# Full_Bridge_Inverter.net
KiCad netlist of a schematic drawn in Altium Designer
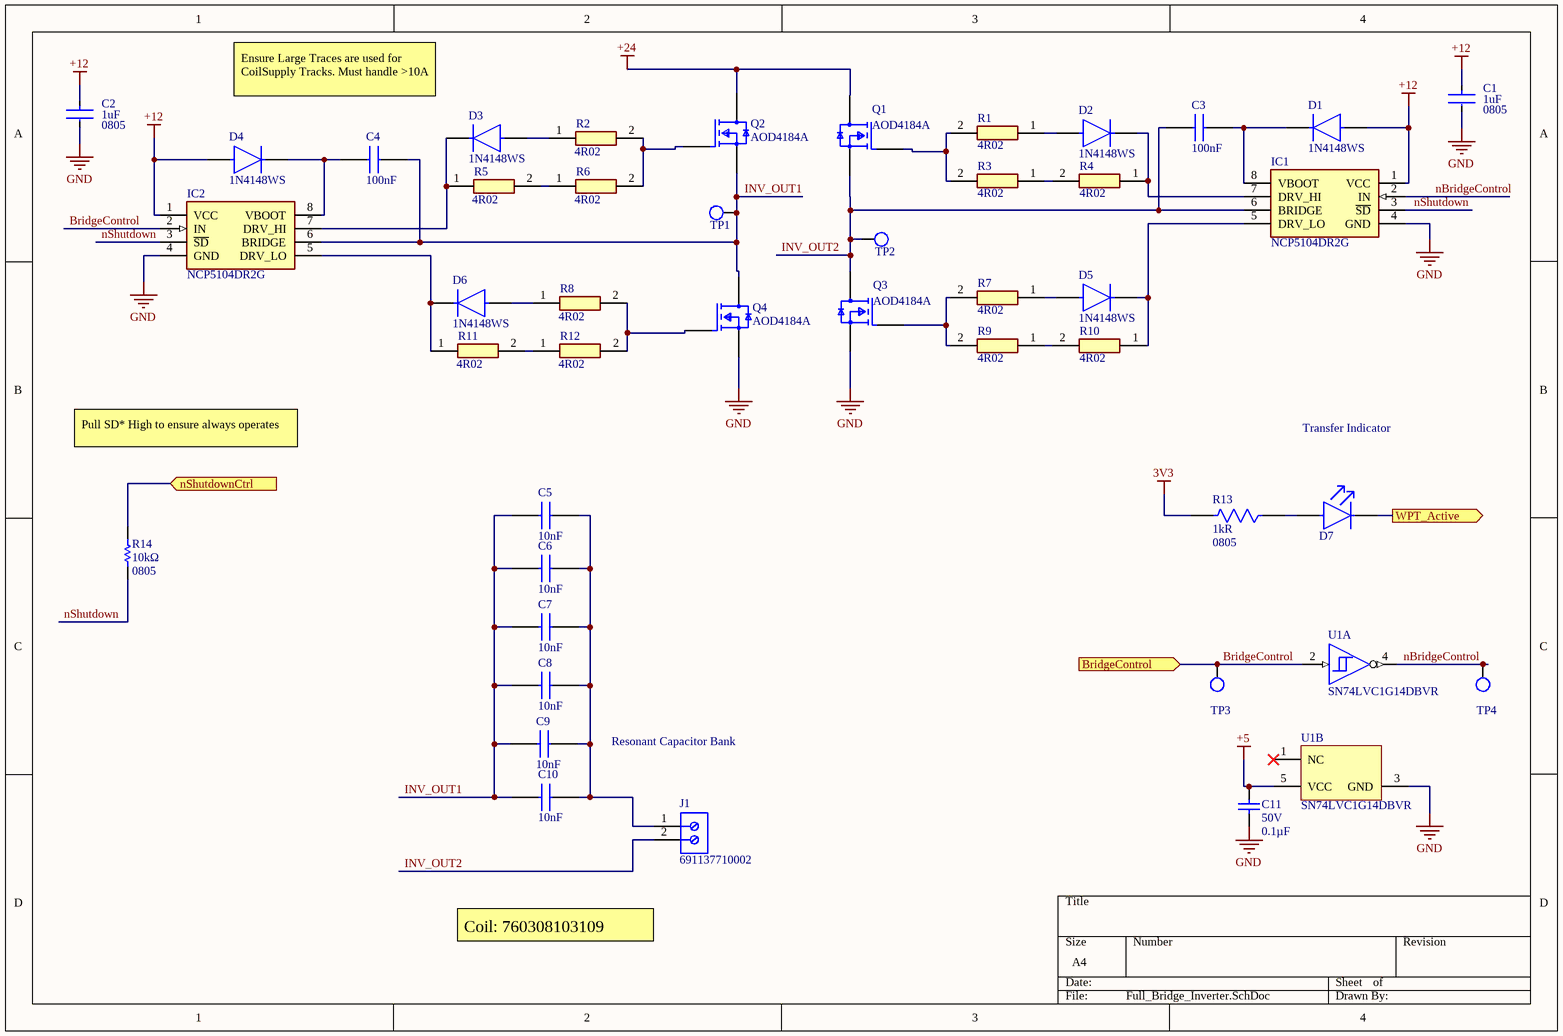
[diagram p0: Full_Bridge_Inverter.SchDoc]

(export (version "E")
  (design (tool "Eeschema 10.0.6"))
  (components
    (comp (ref "C1")
      (value "885012207078")
      (footprint "FP-885012207078-MFG")
      (description "CAP CER 1UF 25V X7R 0805")
      (fields
        (field (name "CAPACITANCE") "1uF")
        (field (name "CASE CODE (IMPERIAL)") "0805")
        (field (name "TOLERANCE") "10%")
      )
      (libsource (lib "Altium Content Vault") (part "b4654b650e69147ec39a6b967a45e02"))
    )
    (comp (ref "C2")
      (value "885012207078")
      (footprint "FP-885012207078-MFG")
      (description "CAP CER 1UF 25V X7R 0805")
      (fields
        (field (name "CAPACITANCE") "1uF")
        (field (name "CASE CODE (IMPERIAL)") "0805")
        (field (name "TOLERANCE") "10%")
      )
      (libsource (lib "Altium Content Vault") (part "b4654b650e69147ec39a6b967a45e02"))
    )
    (comp (ref "C3")
      (value "C0805C104K1RACAUTO7210")
      (footprint "C0805")
      (description "Capacitor")
      (fields (field (name "MOUSER PART NUMBER") "80-C0805C104K1RAUTLR") (field (name "CAPACITANCE") "100nF"))
      (libsource (lib "WPT_Transmitter_lib") (part "C0805C104K1RACAUTO7210"))
    )
    (comp (ref "C4")
      (value "C0805C104K1RACAUTO7210")
      (footprint "C0805")
      (description "Capacitor")
      (fields (field (name "MOUSER PART NUMBER") "80-C0805C104K1RAUTLR") (field (name "CAPACITANCE") "100nF"))
      (libsource (lib "WPT_Transmitter_lib") (part "C0805C104K1RACAUTO7210"))
    )
    (comp (ref "C5")
      (value "C1206C103JAGECAUTO")
      (footprint "SamacSys:CAPC3216X110N")
      (description "Capacitor")
      (fields (field (name "MOUSER PART NUMBER") "80-C1206C103JAGECAUT") (field (name "CAPACITANCE") "10nF"))
      (libsource (lib "*") (part "C1206C103JAGECAUTO"))
    )
    (comp (ref "C6")
      (value "C1206C103JAGECAUTO")
      (footprint "SamacSys:CAPC3216X110N")
      (description "Capacitor")
      (fields (field (name "MOUSER PART NUMBER") "80-C1206C103JAGECAUT") (field (name "CAPACITANCE") "10nF"))
      (libsource (lib "*") (part "C1206C103JAGECAUTO"))
    )
    (comp (ref "C7")
      (value "C1206C103JAGECAUTO")
      (footprint "SamacSys:CAPC3216X110N")
      (description "Capacitor")
      (fields (field (name "MOUSER PART NUMBER") "80-C1206C103JAGECAUT") (field (name "CAPACITANCE") "10nF"))
      (libsource (lib "*") (part "C1206C103JAGECAUTO"))
    )
    (comp (ref "C8")
      (value "C1206C103JAGECAUTO")
      (footprint "SamacSys:CAPC3216X110N")
      (description "Capacitor")
      (fields (field (name "MOUSER PART NUMBER") "80-C1206C103JAGECAUT") (field (name "CAPACITANCE") "10nF"))
      (libsource (lib "*") (part "C1206C103JAGECAUTO"))
    )
    (comp (ref "C9")
      (value "C1206C103JAGECAUTO")
      (footprint "SamacSys:CAPC3216X110N")
      (description "Capacitor")
      (fields (field (name "MOUSER PART NUMBER") "80-C1206C103JAGECAUT") (field (name "CAPACITANCE") "10nF"))
      (libsource (lib "*") (part "C1206C103JAGECAUTO"))
    )
    (comp (ref "C10")
      (value "C1206C103JAGECAUTO")
      (footprint "SamacSys:CAPC3216X110N")
      (description "Capacitor")
      (fields (field (name "MOUSER PART NUMBER") "80-C1206C103JAGECAUT") (field (name "CAPACITANCE") "10nF"))
      (libsource (lib "*") (part "C1206C103JAGECAUTO"))
    )
    (comp (ref "C11")
      (value "C0805C104K5RACTU")
      (footprint "CAP0805")
      (description "CAP CER 0.1UF 50V X7R 0805")
      (fields
        (field (name "TOLERANCE") "±10%")
        (field (name "VOLTAGE - RATED") "50V")
        (field (name "CAPACITANCE") "0.1µF")
      )
      (libsource (lib "Capacitors") (part "C0805C104K5RACTU"))
    )
    (comp (ref "D1")
      (value "1N4148WS")
      (footprint "FP-477AB-IPC_C")
      (description "DIODE GEN PURP 75V 150MA SOD323F")
      (libsource (lib "Altium Content Vault") (part "d7152d700b627762746794eb795d46e"))
    )
    (comp (ref "D2")
      (value "1N4148WS")
      (footprint "FP-477AB-IPC_C")
      (description "DIODE GEN PURP 75V 150MA SOD323F")
      (libsource (lib "Altium Content Vault") (part "d7152d700b627762746794eb795d46e"))
    )
    (comp (ref "D3")
      (value "1N4148WS")
      (footprint "FP-477AB-IPC_C")
      (description "DIODE GEN PURP 75V 150MA SOD323F")
      (libsource (lib "Altium Content Vault") (part "d7152d700b627762746794eb795d46e"))
    )
    (comp (ref "D4")
      (value "1N4148WS")
      (footprint "FP-477AB-IPC_C")
      (description "DIODE GEN PURP 75V 150MA SOD323F")
      (libsource (lib "Altium Content Vault") (part "d7152d700b627762746794eb795d46e"))
    )
    (comp (ref "D5")
      (value "1N4148WS")
      (footprint "FP-477AB-IPC_C")
      (description "DIODE GEN PURP 75V 150MA SOD323F")
      (libsource (lib "Altium Content Vault") (part "d7152d700b627762746794eb795d46e"))
    )
    (comp (ref "D6")
      (value "1N4148WS")
      (footprint "FP-477AB-IPC_C")
      (description "DIODE GEN PURP 75V 150MA SOD323F")
      (libsource (lib "Altium Content Vault") (part "d7152d700b627762746794eb795d46e"))
    )
    (comp (ref "D7")
      (value "150060VS75000")
      (footprint "FP-150060VS75000-MFG")
      (description "LED GREEN CLEAR 0603 SMD")
      (libsource (lib "Altium Content Vault") (part "8706943c75ba83719d021d2fdc84c58"))
    )
    (comp (ref "IC1")
      (value "NCP5104DR2G")
      (footprint "WPT_Transmitter_lib:SOIC127P600X175-8N")
      (description "Integrated Circuit")
      (fields (field (name "MOUSER PART NUMBER") "863-NCP5104DR2G"))
      (libsource (lib "") (part "NCP5104DR2G_1"))
    )
    (comp (ref "IC2")
      (value "NCP5104DR2G")
      (footprint "WPT_Transmitter_lib:SOIC127P600X175-8N")
      (description "Integrated Circuit")
      (fields (field (name "MOUSER PART NUMBER") "863-NCP5104DR2G"))
      (libsource (lib "WPT_Transmitter_lib") (part "NCP5104DR2G"))
    )
    (comp (ref "J1")
      (value "691137710002")
      (footprint "691137710002")
      (description "Series 1377 - 5.00 mm Horizontal Entry with Pressure Clamp WR-TBL, 2 pin")
      (fields (field (name "MANUFACTURER") "Wurth Elektronik") (field (name "PUBLISHER") "WurthElektronik"))
      (libsource (lib "Altium Content Vault") (part "WE-CN-1P-F-TB2"))
    )
    (comp (ref "Q1")
      (value "AOD4184A")
      (footprint "FP-TO252-MFG")
      (description "MOSFET N-CH 40V 50A TO252")
      (libsource (lib "Altium Content Vault") (part "eaf820099600a16e7148a0c70285cb7"))
    )
    (comp (ref "Q2")
      (value "AOD4184A")
      (footprint "FP-TO252-MFG")
      (description "MOSFET N-CH 40V 50A TO252")
      (libsource (lib "Altium Content Vault") (part "eaf820099600a16e7148a0c70285cb7"))
    )
    (comp (ref "Q3")
      (value "AOD4184A")
      (footprint "FP-TO252-MFG")
      (description "MOSFET N-CH 40V 50A TO252")
      (libsource (lib "Altium Content Vault") (part "eaf820099600a16e7148a0c70285cb7"))
    )
    (comp (ref "Q4")
      (value "AOD4184A")
      (footprint "FP-TO252-MFG")
      (description "MOSFET N-CH 40V 50A TO252")
      (libsource (lib "Altium Content Vault") (part "eaf820099600a16e7148a0c70285cb7"))
    )
    (comp (ref "R1")
      (value "RMCF1206FT4R02")
      (footprint "WPT_Transmitter_lib:RESC3216X70N")
      (description "Resistor")
      (fields (field (name "RESISTANCE") "4R02"))
      (libsource (lib "") (part "RMCF1206FT4R02_1"))
    )
    (comp (ref "R2")
      (value "RMCF1206FT4R02")
      (footprint "WPT_Transmitter_lib:RESC3216X70N")
      (description "Resistor")
      (fields (field (name "RESISTANCE") "4R02"))
      (libsource (lib "WPT_Transmitter_lib") (part "RMCF1206FT4R02"))
    )
    (comp (ref "R3")
      (value "RMCF1206FT4R02")
      (footprint "WPT_Transmitter_lib:RESC3216X70N")
      (description "Resistor")
      (fields (field (name "RESISTANCE") "4R02"))
      (libsource (lib "") (part "RMCF1206FT4R02_1"))
    )
    (comp (ref "R4")
      (value "RMCF1206FT4R02")
      (footprint "WPT_Transmitter_lib:RESC3216X70N")
      (description "Resistor")
      (fields (field (name "RESISTANCE") "4R02"))
      (libsource (lib "") (part "RMCF1206FT4R02_1"))
    )
    (comp (ref "R5")
      (value "RMCF1206FT4R02")
      (footprint "WPT_Transmitter_lib:RESC3216X70N")
      (description "Resistor")
      (fields (field (name "RESISTANCE") "4R02"))
      (libsource (lib "WPT_Transmitter_lib") (part "RMCF1206FT4R02"))
    )
    (comp (ref "R6")
      (value "RMCF1206FT4R02")
      (footprint "WPT_Transmitter_lib:RESC3216X70N")
      (description "Resistor")
      (fields (field (name "RESISTANCE") "4R02"))
      (libsource (lib "WPT_Transmitter_lib") (part "RMCF1206FT4R02"))
    )
    (comp (ref "R7")
      (value "RMCF1206FT4R02")
      (footprint "WPT_Transmitter_lib:RESC3216X70N")
      (description "Resistor")
      (fields (field (name "RESISTANCE") "4R02"))
      (libsource (lib "") (part "RMCF1206FT4R02_1"))
    )
    (comp (ref "R8")
      (value "RMCF1206FT4R02")
      (footprint "WPT_Transmitter_lib:RESC3216X70N")
      (description "Resistor")
      (fields (field (name "RESISTANCE") "4R02"))
      (libsource (lib "WPT_Transmitter_lib") (part "RMCF1206FT4R02"))
    )
    (comp (ref "R9")
      (value "RMCF1206FT4R02")
      (footprint "WPT_Transmitter_lib:RESC3216X70N")
      (description "Resistor")
      (fields (field (name "RESISTANCE") "4R02"))
      (libsource (lib "") (part "RMCF1206FT4R02_1"))
    )
    (comp (ref "R10")
      (value "RMCF1206FT4R02")
      (footprint "WPT_Transmitter_lib:RESC3216X70N")
      (description "Resistor")
      (fields (field (name "RESISTANCE") "4R02"))
      (libsource (lib "") (part "RMCF1206FT4R02_1"))
    )
    (comp (ref "R11")
      (value "RMCF1206FT4R02")
      (footprint "WPT_Transmitter_lib:RESC3216X70N")
      (description "Resistor")
      (fields (field (name "RESISTANCE") "4R02"))
      (libsource (lib "WPT_Transmitter_lib") (part "RMCF1206FT4R02"))
    )
    (comp (ref "R12")
      (value "RMCF1206FT4R02")
      (footprint "WPT_Transmitter_lib:RESC3216X70N")
      (description "Resistor")
      (fields (field (name "RESISTANCE") "4R02"))
      (libsource (lib "WPT_Transmitter_lib") (part "RMCF1206FT4R02"))
    )
    (comp (ref "R13")
      (value "RNCP0805FTD1K00")
      (footprint "FP-RNCP0805-MFG")
      (description "1kΩ ±1% 0.25W 0805 High Power Anti-Sulfur Thin Film Chip Resistor")
      (fields
        (field (name "RESISTANCE") "1kR")
        (field (name "SIZE CODE") "0805")
        (field (name "TOLERANCE") "1%")
      )
      (libsource (lib "Altium Content Vault") (part "1029c3af85768c4190bb7ad29bc67b5"))
    )
    (comp (ref "R14")
      (value "RC0805FR-0710KL")
      (footprint "RES0805")
      (description "RES SMD 10K OHM 1% 1/8W 0805")
      (fields
        (field (name "MANUFACTURER") "Yageo")
        (field (name "TOLERANCE") "±1%")
        (field (name "RESISTANCE") "10kΩ")
        (field (name "PACKAGE / CASE") "0805")
      )
      (libsource (lib "Resistors") (part "RC0805FR-0710KL"))
    )
    (comp (ref "TP1")
      (value "Bridge 1")
      (footprint "TESTPOINT_LOOP")
      (description "PC TEST POINT MINIATURE WHITE")
      (libsource (lib "Connectors and Headers") (part "TESTPOINT_LOOP"))
    )
    (comp (ref "TP2")
      (value "Bridge 2")
      (footprint "TESTPOINT_LOOP")
      (description "PC TEST POINT MINIATURE WHITE")
      (libsource (lib "Connectors and Headers") (part "TESTPOINT_LOOP"))
    )
    (comp (ref "TP3")
      (value "Oscillator Out")
      (footprint "TESTPOINT_LOOP")
      (description "PC TEST POINT MINIATURE WHITE")
      (libsource (lib "Connectors and Headers") (part "TESTPOINT_LOOP"))
    )
    (comp (ref "TP4")
      (value "NOT Oscillator Out")
      (footprint "TESTPOINT_LOOP")
      (description "PC TEST POINT MINIATURE WHITE")
      (libsource (lib "Connectors and Headers") (part "TESTPOINT_LOOP"))
    )
    (comp (ref "U1")
      (value "SN74LVC1G14DBVR")
      (footprint "DBV0005A_L")
      (description "Single Schmitt-Trigger Inverter, DBV0005A, LARGE T&R")
      (fields
        (field (name "GENERIC PART NUMBER") "SN74LVC1G14")
        (field (name "MANUFACTURER") "Texas Instruments")
      )
      (libsource (lib "Altium Content Vault") (part "TI-SN74XXX1XX4-XX-5-SCHMITT"))
    )
  )
  (nets
    (net (code "1") (name "+5") (class "Default")
      (node (ref "C11") (pin "2") (pinfunction "2_2") (pintype "passive"))
      (node (ref "U1") (pin "5") (pinfunction "VCC_5") (pintype "power_in"))
    )
    (net (code "2") (name "+12") (class "Default")
      (node (ref "C1") (pin "1") (pinfunction "1_1") (pintype "passive"))
      (node (ref "C2") (pin "1") (pinfunction "1_1") (pintype "passive"))
      (node (ref "D1") (pin "2") (pinfunction "A_2") (pintype "passive"))
      (node (ref "D4") (pin "2") (pinfunction "A_2") (pintype "passive"))
      (node (ref "IC1") (pin "1") (pinfunction "VCC_1") (pintype "power_in"))
      (node (ref "IC2") (pin "1") (pinfunction "VCC_1") (pintype "power_in"))
    )
    (net (code "3") (name "+24") (class "Default")
      (node (ref "Q1") (pin "4") (pinfunction "D_4") (pintype "passive"))
      (node (ref "Q2") (pin "4") (pinfunction "D_4") (pintype "passive"))
    )
    (net (code "4") (name "/BridgeControl") (class "Default")
      (node (ref "IC2") (pin "2") (pinfunction "IN_2") (pintype "input"))
      (node (ref "TP3") (pin "1") (pintype "passive"))
      (node (ref "U1") (pin "2") (pinfunction "A_2") (pintype "input"))
    )
    (net (code "5") (name "/INV_OUT1") (class "Default")
      (node (ref "C10") (pin "2") (pinfunction "2_2") (pintype "passive"))
      (node (ref "C4") (pin "2") (pinfunction "2_2") (pintype "passive"))
      (node (ref "C5") (pin "1") (pinfunction "1_1") (pintype "passive"))
      (node (ref "C6") (pin "1") (pinfunction "1_1") (pintype "passive"))
      (node (ref "C7") (pin "1") (pinfunction "1_1") (pintype "passive"))
      (node (ref "C8") (pin "2") (pinfunction "2_2") (pintype "passive"))
      (node (ref "C9") (pin "2") (pinfunction "2_2") (pintype "passive"))
      (node (ref "IC2") (pin "6") (pinfunction "BRIDGE_6") (pintype "passive"))
      (node (ref "Q2") (pin "3") (pinfunction "S_3") (pintype "passive"))
      (node (ref "Q4") (pin "4") (pinfunction "D_4") (pintype "passive"))
      (node (ref "TP1") (pin "1") (pintype "passive"))
    )
    (net (code "6") (name "/INV_OUT2") (class "Default")
      (node (ref "C3") (pin "1") (pinfunction "1_1") (pintype "passive"))
      (node (ref "IC1") (pin "6") (pinfunction "BRIDGE_6") (pintype "passive"))
      (node (ref "J1") (pin "2") (pinfunction "2_2") (pintype "passive"))
      (node (ref "Q1") (pin "3") (pinfunction "S_3") (pintype "passive"))
      (node (ref "Q3") (pin "4") (pinfunction "D_4") (pintype "passive"))
      (node (ref "TP2") (pin "1") (pintype "passive"))
    )
    (net (code "7") (name "/WPT_Active") (class "Default")
      (node (ref "D7") (pin "1") (pinfunction "C_1") (pintype "passive"))
    )
    (net (code "8") (name "/nBridgeControl") (class "Default")
      (node (ref "IC1") (pin "2") (pinfunction "IN_2") (pintype "input"))
      (node (ref "TP4") (pin "1") (pintype "passive"))
      (node (ref "U1") (pin "4") (pinfunction "Y_4") (pintype "output"))
    )
    (net (code "9") (name "/nShutdown") (class "Default")
      (node (ref "IC1") (pin "3") (pinfunction "~{SD}_3") (pintype "passive"))
      (node (ref "IC2") (pin "3") (pinfunction "~{SD}_3") (pintype "passive"))
      (node (ref "R14") (pin "1") (pinfunction "1_1") (pintype "passive"))
    )
    (net (code "10") (name "/nShutdownCtrl") (class "Default")
      (node (ref "R14") (pin "2") (pinfunction "2_2") (pintype "passive"))
    )
    (net (code "11") (name "3V3") (class "Default")
      (node (ref "R13") (pin "2") (pinfunction "2_2") (pintype "passive"))
    )
    (net (code "12") (name "GND") (class "Default")
      (node (ref "C1") (pin "2") (pinfunction "2_2") (pintype "passive"))
      (node (ref "C11") (pin "1") (pinfunction "1_1") (pintype "passive"))
      (node (ref "C2") (pin "2") (pinfunction "2_2") (pintype "passive"))
      (node (ref "IC1") (pin "4") (pinfunction "GND_4") (pintype "power_in"))
      (node (ref "IC2") (pin "4") (pinfunction "GND_4") (pintype "power_in"))
      (node (ref "Q3") (pin "3") (pinfunction "S_3") (pintype "passive"))
      (node (ref "Q4") (pin "3") (pinfunction "S_3") (pintype "passive"))
      (node (ref "U1") (pin "3") (pinfunction "GND_3") (pintype "power_in"))
    )
    (net (code "13") (name "Net-(C10-Pad1)") (class "Default")
      (node (ref "C10") (pin "1") (pinfunction "1_1") (pintype "passive"))
      (node (ref "C5") (pin "2") (pinfunction "2_2") (pintype "passive"))
      (node (ref "C6") (pin "2") (pinfunction "2_2") (pintype "passive"))
      (node (ref "C7") (pin "2") (pinfunction "2_2") (pintype "passive"))
      (node (ref "C8") (pin "1") (pinfunction "1_1") (pintype "passive"))
      (node (ref "C9") (pin "1") (pinfunction "1_1") (pintype "passive"))
      (node (ref "J1") (pin "1") (pinfunction "1_1") (pintype "passive"))
    )
    (net (code "14") (name "Net-(D1-C)") (class "Default")
      (node (ref "C3") (pin "2") (pinfunction "2_2") (pintype "passive"))
      (node (ref "D1") (pin "1") (pinfunction "C_1") (pintype "passive"))
      (node (ref "IC1") (pin "8") (pinfunction "VBOOT_8") (pintype "passive"))
    )
    (net (code "15") (name "Net-(D2-A)") (class "Default")
      (node (ref "D2") (pin "2") (pinfunction "A_2") (pintype "passive"))
      (node (ref "R1") (pin "1") (pinfunction "1_1") (pintype "passive"))
    )
    (net (code "16") (name "Net-(D2-C)") (class "Default")
      (node (ref "D2") (pin "1") (pinfunction "C_1") (pintype "passive"))
      (node (ref "IC1") (pin "7") (pinfunction "DRV_HI_7") (pintype "passive"))
      (node (ref "R4") (pin "1") (pinfunction "1_1") (pintype "passive"))
    )
    (net (code "17") (name "Net-(D3-A)") (class "Default")
      (node (ref "D3") (pin "2") (pinfunction "A_2") (pintype "passive"))
      (node (ref "R2") (pin "1") (pinfunction "1_1") (pintype "passive"))
    )
    (net (code "18") (name "Net-(D3-C)") (class "Default")
      (node (ref "D3") (pin "1") (pinfunction "C_1") (pintype "passive"))
      (node (ref "IC2") (pin "7") (pinfunction "DRV_HI_7") (pintype "passive"))
      (node (ref "R5") (pin "1") (pinfunction "1_1") (pintype "passive"))
    )
    (net (code "19") (name "Net-(D4-C)") (class "Default")
      (node (ref "C4") (pin "1") (pinfunction "1_1") (pintype "passive"))
      (node (ref "D4") (pin "1") (pinfunction "C_1") (pintype "passive"))
      (node (ref "IC2") (pin "8") (pinfunction "VBOOT_8") (pintype "passive"))
    )
    (net (code "20") (name "Net-(D5-A)") (class "Default")
      (node (ref "D5") (pin "2") (pinfunction "A_2") (pintype "passive"))
      (node (ref "R7") (pin "1") (pinfunction "1_1") (pintype "passive"))
    )
    (net (code "21") (name "Net-(D5-C)") (class "Default")
      (node (ref "D5") (pin "1") (pinfunction "C_1") (pintype "passive"))
      (node (ref "IC1") (pin "5") (pinfunction "DRV_LO_5") (pintype "passive"))
      (node (ref "R10") (pin "1") (pinfunction "1_1") (pintype "passive"))
    )
    (net (code "22") (name "Net-(D6-A)") (class "Default")
      (node (ref "D6") (pin "2") (pinfunction "A_2") (pintype "passive"))
      (node (ref "R8") (pin "1") (pinfunction "1_1") (pintype "passive"))
    )
    (net (code "23") (name "Net-(D6-C)") (class "Default")
      (node (ref "D6") (pin "1") (pinfunction "C_1") (pintype "passive"))
      (node (ref "IC2") (pin "5") (pinfunction "DRV_LO_5") (pintype "passive"))
      (node (ref "R11") (pin "1") (pinfunction "1_1") (pintype "passive"))
    )
    (net (code "24") (name "Net-(D7-A)") (class "Default")
      (node (ref "D7") (pin "2") (pinfunction "A_2") (pintype "passive"))
      (node (ref "R13") (pin "1") (pinfunction "1_1") (pintype "passive"))
    )
    (net (code "25") (name "Net-(Q1-G)") (class "Default")
      (node (ref "Q1") (pin "1") (pinfunction "G_1") (pintype "passive"))
      (node (ref "R1") (pin "2") (pinfunction "2_2") (pintype "passive"))
      (node (ref "R3") (pin "2") (pinfunction "2_2") (pintype "passive"))
    )
    (net (code "26") (name "Net-(Q2-G)") (class "Default")
      (node (ref "Q2") (pin "1") (pinfunction "G_1") (pintype "passive"))
      (node (ref "R2") (pin "2") (pinfunction "2_2") (pintype "passive"))
      (node (ref "R6") (pin "2") (pinfunction "2_2") (pintype "passive"))
    )
    (net (code "27") (name "Net-(Q3-G)") (class "Default")
      (node (ref "Q3") (pin "1") (pinfunction "G_1") (pintype "passive"))
      (node (ref "R7") (pin "2") (pinfunction "2_2") (pintype "passive"))
      (node (ref "R9") (pin "2") (pinfunction "2_2") (pintype "passive"))
    )
    (net (code "28") (name "Net-(Q4-G)") (class "Default")
      (node (ref "Q4") (pin "1") (pinfunction "G_1") (pintype "passive"))
      (node (ref "R12") (pin "2") (pinfunction "2_2") (pintype "passive"))
      (node (ref "R8") (pin "2") (pinfunction "2_2") (pintype "passive"))
    )
    (net (code "29") (name "Net-(R3-Pad1)") (class "Default")
      (node (ref "R3") (pin "1") (pinfunction "1_1") (pintype "passive"))
      (node (ref "R4") (pin "2") (pinfunction "2_2") (pintype "passive"))
    )
    (net (code "30") (name "Net-(R5-Pad2)") (class "Default")
      (node (ref "R5") (pin "2") (pinfunction "2_2") (pintype "passive"))
      (node (ref "R6") (pin "1") (pinfunction "1_1") (pintype "passive"))
    )
    (net (code "31") (name "Net-(R10-Pad2)") (class "Default")
      (node (ref "R10") (pin "2") (pinfunction "2_2") (pintype "passive"))
      (node (ref "R9") (pin "1") (pinfunction "1_1") (pintype "passive"))
    )
    (net (code "32") (name "Net-(R11-Pad2)") (class "Default")
      (node (ref "R11") (pin "2") (pinfunction "2_2") (pintype "passive"))
      (node (ref "R12") (pin "1") (pinfunction "1_1") (pintype "passive"))
    )
    (net (code "33") (name "unconnected-(U1B-NC-Pad1)") (class "Default")
      (node (ref "U1") (pin "1") (pinfunction "NC_1") (pintype "passive+no_connect"))
    )
  )
)
